# FHJController_V5_0_Main.net
KiCad netlist of a schematic drawn in Altium Designer
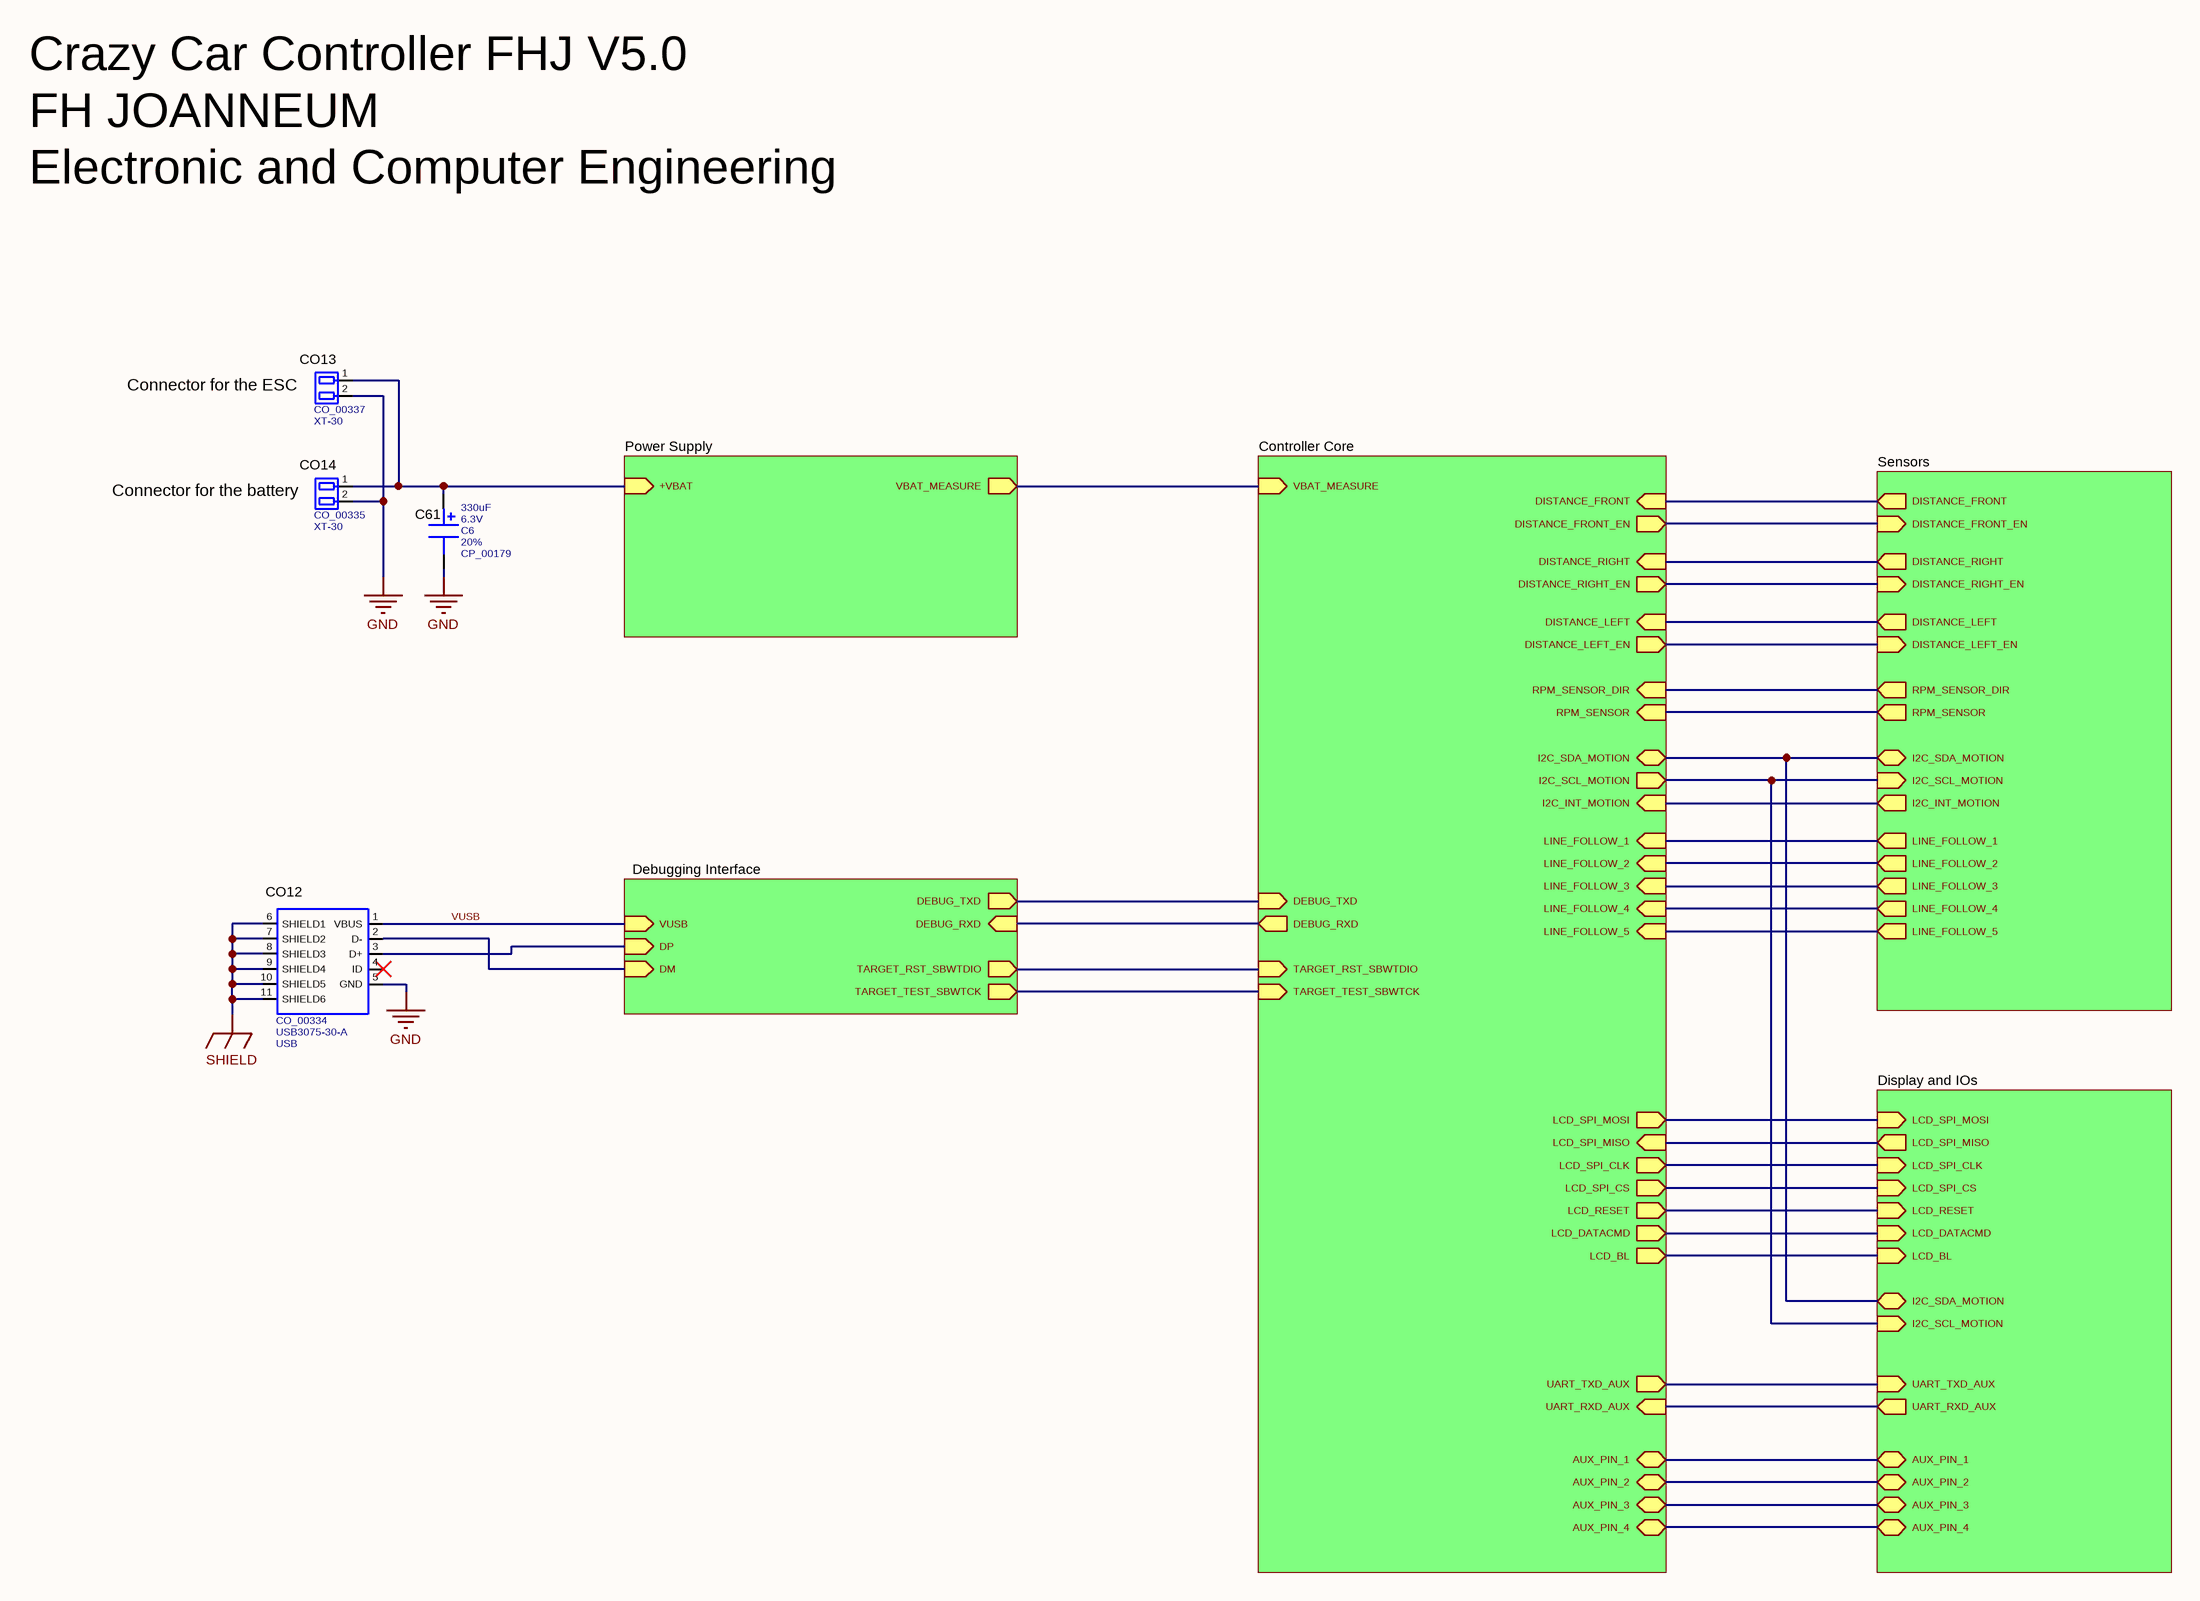
[diagram p0: FHJController_V5.0_Main.SchDoc]

(export (version "E")
  (design (tool "Eeschema 10.0.6"))
  (components
    (comp (ref "C61")
      (value "capacitor_polar")
      (footprint "CP_00179L")
      (fields
        (field (name "CAPACITANCE") "330uF")
        (field (name "VOLTAGE") "6.3V")
        (field (name "PACKAGE") "C6")
        (field (name "TOLERANCE") "20%")
        (field (name "PART_NUMBER") "CP_00179")
        (field (name "CREATOR") "Krenn Markus")
      )
      (libsource (lib "Central Library") (part "capacitor_polar"))
    )
    (comp (ref "CO12")
      (value "CO_00334")
      (footprint "CO_00334N")
      (description "Micro-USB Typ B, USB 2.0, Buchse, 5 -polig, Oberflächenmontage, Rechtwinklig")
      (fields
        (field (name "POWER") "0W")
        (field (name "PART_NUMBER") "CO_00334")
        (field (name "MANUFACTURER_NUMBER") "USB3075-30-A")
        (field (name "CONNECTOR_TYPE") "USB")
        (field (name "CREATOR") "Krenn Markus")
      )
      (libsource (lib "Central Library") (part "CO_00334"))
    )
    (comp (ref "CO13")
      (value "header1x2")
      (footprint "CO_00337N")
      (description "DYMOND XT-30 BEC Stecker")
      (fields
        (field (name "POWER") "0W")
        (field (name "PART_NUMBER") "CO_00337")
        (field (name "MANUFACTURER_NUMBER") "XT-30")
        (field (name "CREATOR") "Krenn Markus")
      )
      (libsource (lib "Central Library") (part "header1x2"))
    )
    (comp (ref "CO14")
      (value "header1x2")
      (footprint "CO_00335N")
      (description "DYMOND XT-30 BEC Stecker")
      (fields
        (field (name "POWER") "0W")
        (field (name "PART_NUMBER") "CO_00335")
        (field (name "MANUFACTURER_NUMBER") "XT-30")
        (field (name "CREATOR") "Krenn Markus")
      )
      (libsource (lib "Central Library") (part "header1x2"))
    )
  )
  (nets
    (net (code "1") (name "/+VBAT") (class "Default")
      (node (ref "C61") (pin "1") (pinfunction "PIN1_1") (pintype "passive"))
      (node (ref "CO13") (pin "1") (pinfunction "PIN1_1") (pintype "passive"))
      (node (ref "CO14") (pin "1") (pinfunction "PIN1_1") (pintype "passive"))
    )
    (net (code "14") (name "/DM") (class "Default")
      (node (ref "CO12") (pin "2") (pinfunction "D-_2") (pintype "passive"))
    )
    (net (code "15") (name "/DP") (class "Default")
      (node (ref "CO12") (pin "3") (pinfunction "D+_3") (pintype "passive"))
    )
    (net (code "38") (name "/VUSB") (class "Default")
      (node (ref "CO12") (pin "1") (pinfunction "VBUS_1") (pintype "passive"))
    )
    (net (code "39") (name "GND") (class "Default")
      (node (ref "C61") (pin "2") (pinfunction "PIN2_2") (pintype "passive"))
      (node (ref "CO12") (pin "5") (pinfunction "GND_5") (pintype "passive"))
      (node (ref "CO13") (pin "2") (pinfunction "PIN2_2") (pintype "passive"))
      (node (ref "CO14") (pin "2") (pinfunction "PIN2_2") (pintype "passive"))
    )
    (net (code "40") (name "SHIELD") (class "Default")
      (node (ref "CO12") (pin "10") (pinfunction "SHIELD5_10") (pintype "passive"))
      (node (ref "CO12") (pin "11") (pinfunction "SHIELD6_11") (pintype "passive"))
      (node (ref "CO12") (pin "6") (pinfunction "SHIELD1_6") (pintype "passive"))
      (node (ref "CO12") (pin "7") (pinfunction "SHIELD2_7") (pintype "passive"))
      (node (ref "CO12") (pin "8") (pinfunction "SHIELD3_8") (pintype "passive"))
      (node (ref "CO12") (pin "9") (pinfunction "SHIELD4_9") (pintype "passive"))
    )
    (net (code "41") (name "unconnected-(CO12-ID-Pad4)") (class "Default")
      (node (ref "CO12") (pin "4") (pinfunction "ID_4") (pintype "passive+no_connect"))
    )
  )
)
